# SynchConv_sch.net
KiCad netlist of a schematic drawn in Altium Designer
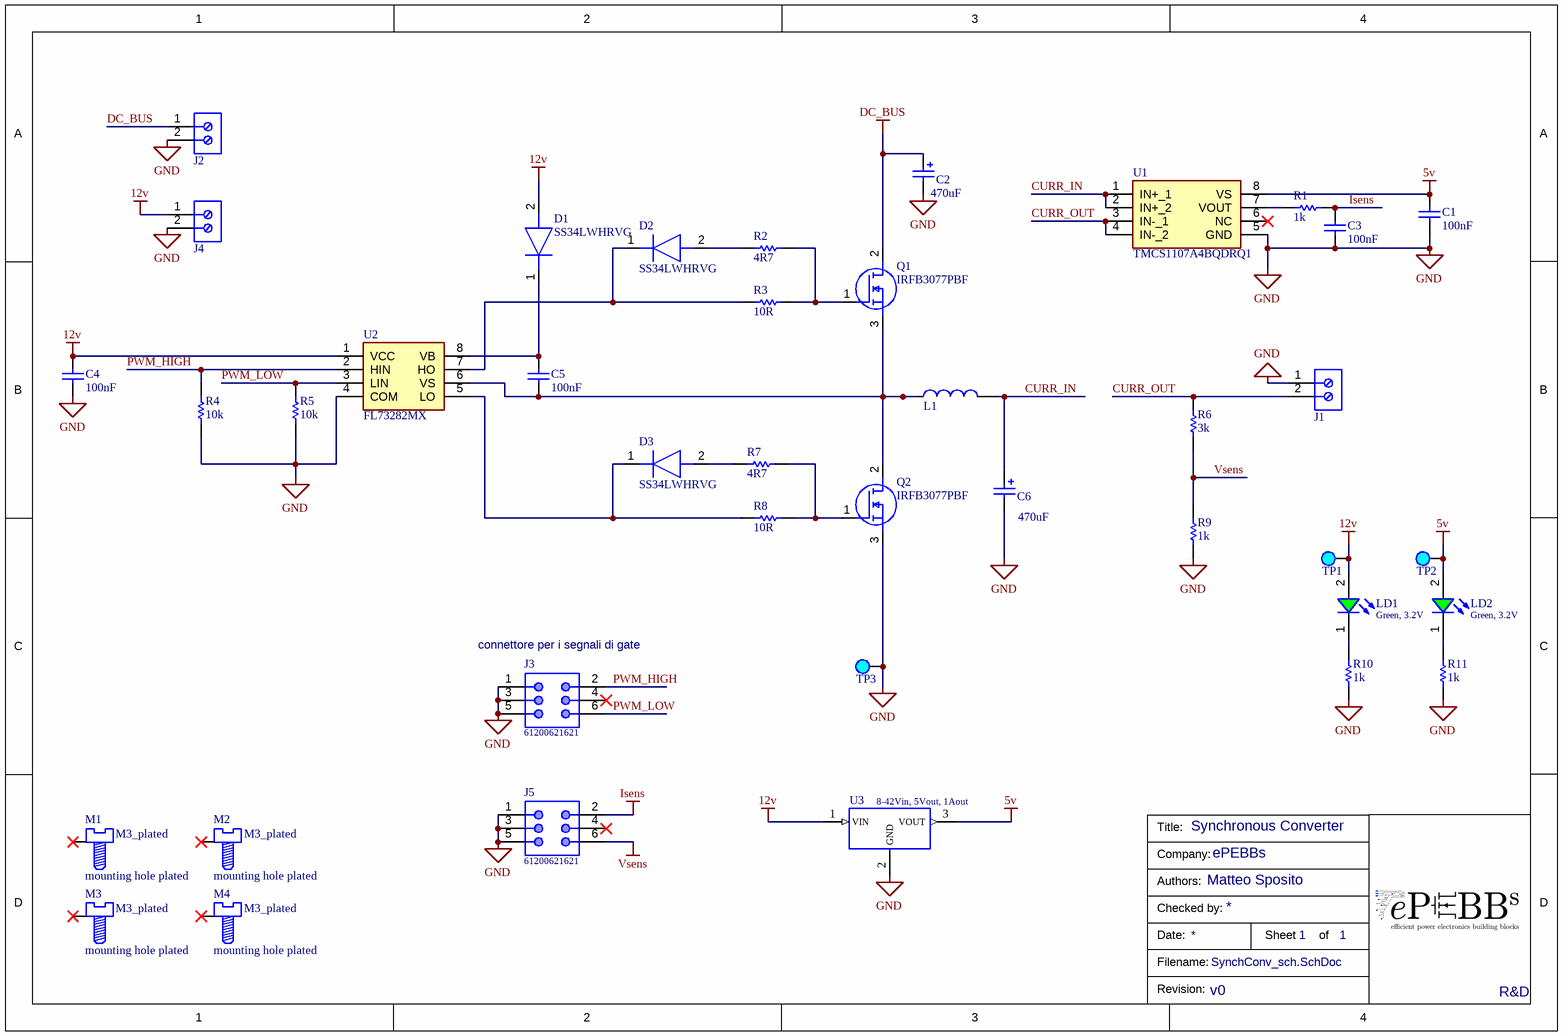
[diagram p0: SynchConv_sch.SchDoc]

(export (version "E")
  (design (tool "Eeschema 10.0.6"))
  (components
    (comp (ref "C1")
      (value "100nF")
      (footprint "CAP_0805")
      (description "capacitor 0805")
      (fields
        (field (name "MANUFACTURER PART NUMBER") "885012207098")
        (field (name "MANUFACTURER") "Wurth Elektronik")
      )
      (libsource (lib "ePEBBs_lib_sch") (part "Cap_0805"))
    )
    (comp (ref "C2")
      (value "470uF")
      (footprint "WCAP-ATG5_D13H20")
      (description "WCAP-ATG5 Aluminum Electrolytic Capacitor, Radial THT, D13xH20mm, 470uF, 63V")
      (fields
        (field (name "MANUFACTURER") "Wurth Elektronik")
        (field (name "MANUFACTURER PART NUMBER") "860020778021")
      )
      (libsource (lib "ePEBBs_lib_sch") (part "860020778021"))
    )
    (comp (ref "C3")
      (value "100nF")
      (footprint "CAP_0805")
      (description "capacitor 0805")
      (fields
        (field (name "MANUFACTURER PART NUMBER") "885012207098")
        (field (name "MANUFACTURER") "Wurth Elektronik")
      )
      (libsource (lib "ePEBBs_lib_sch") (part "Cap_0805"))
    )
    (comp (ref "C4")
      (value "100nF")
      (footprint "CAP_0805")
      (description "capacitor 0805")
      (fields
        (field (name "MANUFACTURER PART NUMBER") "885012207098")
        (field (name "MANUFACTURER") "Wurth Elektronik")
      )
      (libsource (lib "ePEBBs_lib_sch") (part "Cap_0805"))
    )
    (comp (ref "C5")
      (value "100nF")
      (footprint "CAP_0805")
      (description "capacitor 0805")
      (fields
        (field (name "MANUFACTURER PART NUMBER") "885012207098")
        (field (name "MANUFACTURER") "Wurth Elektronik")
      )
      (libsource (lib "ePEBBs_lib_sch") (part "Cap_0805"))
    )
    (comp (ref "C6")
      (value "470uF")
      (footprint "WCAP-ATG5_D13H20")
      (description "WCAP-ATG5 Aluminum Electrolytic Capacitor, Radial THT, D13xH20mm, 470uF, 63V")
      (fields
        (field (name "MANUFACTURER") "Wurth Elektronik")
        (field (name "MANUFACTURER PART NUMBER") "860020778021")
      )
      (libsource (lib "ePEBBs_lib_sch") (part "860020778021"))
    )
    (comp (ref "D1")
      (value "SS34LWHRVG")
      (footprint "SamacSys:SODFL3718X102N")
      (description "Diode")
      (fields (field (name "MOUSER PART NUMBER") "821-SS34LWHRVG"))
      (libsource (lib "*") (part "SS34LWHRVG"))
    )
    (comp (ref "D2")
      (value "SS34LWHRVG")
      (footprint "SamacSys:SODFL3718X102N")
      (description "Diode")
      (fields (field (name "MOUSER PART NUMBER") "821-SS34LWHRVG"))
      (libsource (lib "*") (part "SS34LWHRVG"))
    )
    (comp (ref "D3")
      (value "SS34LWHRVG")
      (footprint "SamacSys:SODFL3718X102N")
      (description "Diode")
      (fields (field (name "MOUSER PART NUMBER") "821-SS34LWHRVG"))
      (libsource (lib "*") (part "SS34LWHRVG"))
    )
    (comp (ref "J1")
      (value "691502710002")
      (footprint "691502710002")
      (description "WR-TBL Series 5027 Horizontal Entry Modular, Through Hole, pitch 5mm, 2p")
      (fields (field (name "MANUFACTURER") "Wurth Elektronik"))
      (libsource (lib "For IntLib") (part "691502710002"))
    )
    (comp (ref "J2")
      (value "691502710002")
      (footprint "691502710002")
      (description "WR-TBL Series 5027 Horizontal Entry Modular, Through Hole, pitch 5mm, 2p")
      (fields (field (name "MANUFACTURER") "Wurth Elektronik"))
      (libsource (lib "ePEBBs_lib_sch") (part "691502710002"))
    )
    (comp (ref "J3")
      (value "61200621621")
      (footprint "61200621621")
      (description "WR-BHD Box Header, Male PCB side, pitch 2.54mm, THT, Straight, 6p")
      (fields (field (name "MANUFACTURER") "Wurth Elektronik"))
      (libsource (lib "ePEBBs_lib_sch") (part "61200621621"))
    )
    (comp (ref "J4")
      (value "691502710002")
      (footprint "691502710002")
      (description "WR-TBL Series 5027 Horizontal Entry Modular, Through Hole, pitch 5mm, 2p")
      (fields (field (name "MANUFACTURER") "Wurth Elektronik"))
      (libsource (lib "ePEBBs_lib_sch") (part "691502710002"))
    )
    (comp (ref "J5")
      (value "61200621621")
      (footprint "61200621621")
      (description "WR-BHD Box Header, Male PCB side, pitch 2.54mm, THT, Straight, 6p")
      (fields (field (name "MANUFACTURER") "Wurth Elektronik"))
      (libsource (lib "ePEBBs_lib_sch") (part "61200621621"))
    )
    (comp (ref "L1")
      (value "59µH, 5.4A")
      (footprint "744134")
      (description "WE-SI THT Leaded Toroidal Storage Choke, 59µH, 5.4A, 0.05Ω")
      (fields
        (field (name "MANUFACTURER PART NUMBER") "744134")
        (field (name "MANUFACTURER") "Wurth Elektronik")
      )
      (libsource (lib "ePEBBs_lib_sch") (part "744134"))
    )
    (comp (ref "LD1")
      (value "Green, 3.2V")
      (footprint "WL-SMCW_0805")
      (description "WL-SMCW SMT Mono-color Chip LED Waterclear, size 0805, Green, 3.2V, 140deg")
      (fields (field (name "PART NUMBER") "150080GS75000") (field (name "PUBLISHER") "Wurth Elektronik"))
      (libsource (lib "ePEBBs_lib_sch") (part "150080GS75000"))
    )
    (comp (ref "LD2")
      (value "Green, 3.2V")
      (footprint "WL-SMCW_0805")
      (description "WL-SMCW SMT Mono-color Chip LED Waterclear, size 0805, Green, 3.2V, 140deg")
      (fields (field (name "PART NUMBER") "150080GS75000") (field (name "PUBLISHER") "Wurth Elektronik"))
      (libsource (lib "ePEBBs_lib_sch") (part "150080GS75000"))
    )
    (comp (ref "M1")
      (value "mounting hole plated")
      (footprint "M3_Mountingholes plated")
      (description "M3 plated")
      (libsource (lib "ePEBBs_lib_sch") (part "M3_MountungHole_plated"))
    )
    (comp (ref "M2")
      (value "mounting hole plated")
      (footprint "M3_Mountingholes plated")
      (description "M3 plated")
      (libsource (lib "ePEBBs_lib_sch") (part "M3_MountungHole_plated"))
    )
    (comp (ref "M3")
      (value "mounting hole plated")
      (footprint "M3_Mountingholes plated")
      (description "M3 plated")
      (libsource (lib "ePEBBs_lib_sch") (part "M3_MountungHole_plated"))
    )
    (comp (ref "M4")
      (value "mounting hole plated")
      (footprint "M3_Mountingholes plated")
      (description "M3 plated")
      (libsource (lib "ePEBBs_lib_sch") (part "M3_MountungHole_plated"))
    )
    (comp (ref "Q1")
      (value "IRFB3077PBF")
      (footprint "SamacSys:TO254P483X1016X1994-3P")
      (description "MOSFET (N-Channel)")
      (fields (field (name "MOUSER PART NUMBER") "942-IRFB3077PBF"))
      (libsource (lib "*") (part "IRFB3077PBF"))
    )
    (comp (ref "Q2")
      (value "IRFB3077PBF")
      (footprint "SamacSys:TO254P483X1016X1994-3P")
      (description "MOSFET (N-Channel)")
      (fields (field (name "MOUSER PART NUMBER") "942-IRFB3077PBF"))
      (libsource (lib "*") (part "IRFB3077PBF"))
    )
    (comp (ref "R1")
      (value "1k")
      (footprint "Res_0805")
      (description "SMT Thick Film Resistor, size 0805, 0.125W")
      (fields (field (name "TOLERANCE") "1%"))
      (libsource (lib "ePEBBs_lib_sch") (part "Res_0805"))
    )
    (comp (ref "R2")
      (value "4R7")
      (footprint "Res_0805")
      (description "SMT Thick Film Resistor, size 0805, 0.125W")
      (fields (field (name "TOLERANCE") "1%"))
      (libsource (lib "ePEBBs_lib_sch") (part "Res_0805"))
    )
    (comp (ref "R3")
      (value "10R")
      (footprint "Res_0805")
      (description "SMT Thick Film Resistor, size 0805, 0.125W")
      (fields (field (name "TOLERANCE") "1%"))
      (libsource (lib "ePEBBs_lib_sch") (part "Res_0805"))
    )
    (comp (ref "R4")
      (value "10k")
      (footprint "Res_0805")
      (description "SMT Thick Film Resistor, size 0805, 0.125W")
      (fields (field (name "TOLERANCE") "1%"))
      (libsource (lib "ePEBBs_lib_sch") (part "Res_0805"))
    )
    (comp (ref "R5")
      (value "10k")
      (footprint "Res_0805")
      (description "SMT Thick Film Resistor, size 0805, 0.125W")
      (fields (field (name "TOLERANCE") "1%"))
      (libsource (lib "ePEBBs_lib_sch") (part "Res_0805"))
    )
    (comp (ref "R6")
      (value "3k")
      (footprint "Res_0805")
      (description "SMT Thick Film Resistor, size 0805, 0.125W")
      (fields (field (name "TOLERANCE") "1%"))
      (libsource (lib "ePEBBs_lib_sch") (part "Res_0805"))
    )
    (comp (ref "R7")
      (value "4R7")
      (footprint "Res_0805")
      (description "SMT Thick Film Resistor, size 0805, 0.125W")
      (fields (field (name "TOLERANCE") "1%"))
      (libsource (lib "ePEBBs_lib_sch") (part "Res_0805"))
    )
    (comp (ref "R8")
      (value "10R")
      (footprint "Res_0805")
      (description "SMT Thick Film Resistor, size 0805, 0.125W")
      (fields (field (name "TOLERANCE") "1%"))
      (libsource (lib "ePEBBs_lib_sch") (part "Res_0805"))
    )
    (comp (ref "R9")
      (value "1k")
      (footprint "Res_0805")
      (description "SMT Thick Film Resistor, size 0805, 0.125W")
      (fields (field (name "TOLERANCE") "1%"))
      (libsource (lib "ePEBBs_lib_sch") (part "Res_0805"))
    )
    (comp (ref "R10")
      (value "1k")
      (footprint "Res_0805")
      (description "SMT Thick Film Resistor, size 0805, 0.125W")
      (fields (field (name "TOLERANCE") "1%"))
      (libsource (lib "ePEBBs_lib_sch") (part "Res_0805"))
    )
    (comp (ref "R11")
      (value "1k")
      (footprint "Res_0805")
      (description "SMT Thick Film Resistor, size 0805, 0.125W")
      (fields (field (name "TOLERANCE") "1%"))
      (libsource (lib "ePEBBs_lib_sch") (part "Res_0805"))
    )
    (comp (ref "TP1")
      (value "TP_big")
      (footprint "TP_big")
      (description "test point big")
      (libsource (lib "ePEBBs_lib_sch") (part "TP_big"))
    )
    (comp (ref "TP2")
      (value "TP_big")
      (footprint "TP_big")
      (description "test point big")
      (libsource (lib "ePEBBs_lib_sch") (part "TP_big"))
    )
    (comp (ref "TP3")
      (value "TP_big")
      (footprint "TP_big")
      (description "test point big")
      (libsource (lib "ePEBBs_lib_sch") (part "TP_big"))
    )
    (comp (ref "U1")
      (value "TMCS1107A4BQDRQ1")
      (footprint "SOIC127P600X175-8N")
      (description "SENSOR CURRENT HALL 5.6A 8SOIC")
      (libsource (lib "ePEBBs_lib_sch") (part "TMCS1107A4BQDRQ1"))
    )
    (comp (ref "U2")
      (value "FL73282MX")
      (footprint "SOIC127P600X175-8N")
      (description "Driver di porta 900V Half-Bridge Gate Driver")
      (libsource (lib "ePEBBs_lib_sch") (part "FL73282MX"))
    )
    (comp (ref "U3")
      (value "8-42Vin, 5Vout, 1Aout")
      (footprint "173010x35")
      (description "MagI3C-FDSM Fixed Step Down Regulator Module, SIP-3, 8-36Vin, 5Vout, 1Aout")
      (fields
        (field (name "MANUFACTURER PART NUMBER") "173010542")
        (field (name "PUBLISHER") "Wurth Elektronik")
      )
      (libsource (lib "ePEBBs_lib_sch") (part "173010535"))
    )
  )
  (nets
    (net (code "1") (name "/CURR_IN") (class "Default")
      (node (ref "C6") (pin "1") (pinfunction "P_1") (pintype "passive"))
      (node (ref "L1") (pin "2") (pinfunction "2_2") (pintype "passive"))
      (node (ref "U1") (pin "1") (pinfunction "IN+_1_1") (pintype "passive"))
      (node (ref "U1") (pin "2") (pinfunction "IN+_2_2") (pintype "passive"))
    )
    (net (code "2") (name "/CURR_OUT") (class "Default")
      (node (ref "J1") (pin "2") (pinfunction "2_2") (pintype "passive"))
      (node (ref "R6") (pin "1") (pinfunction "1_1") (pintype "passive"))
      (node (ref "U1") (pin "3") (pinfunction "IN-_1_3") (pintype "passive"))
      (node (ref "U1") (pin "4") (pinfunction "IN-_2_4") (pintype "passive"))
    )
    (net (code "3") (name "/PWM_HIGH") (class "Default")
      (node (ref "J3") (pin "2") (pinfunction "2_2") (pintype "passive"))
      (node (ref "R4") (pin "2") (pinfunction "2_2") (pintype "passive"))
      (node (ref "U2") (pin "2") (pinfunction "HIN_2") (pintype "passive"))
    )
    (net (code "4") (name "/PWM_LOW") (class "Default")
      (node (ref "J3") (pin "6") (pinfunction "6_6") (pintype "passive"))
      (node (ref "R5") (pin "2") (pinfunction "2_2") (pintype "passive"))
      (node (ref "U2") (pin "3") (pinfunction "LIN_3") (pintype "passive"))
    )
    (net (code "5") (name "5v") (class "Default")
      (node (ref "C1") (pin "2") (pinfunction "2_2") (pintype "passive"))
      (node (ref "LD2") (pin "2") (pinfunction "A_2") (pintype "passive"))
      (node (ref "TP2") (pin "1") (pinfunction "1_1") (pintype "passive"))
      (node (ref "U1") (pin "8") (pinfunction "VS_8") (pintype "passive"))
      (node (ref "U3") (pin "3") (pinfunction "VOUT_3") (pintype "output"))
    )
    (net (code "6") (name "12v") (class "Default")
      (node (ref "C4") (pin "2") (pinfunction "2_2") (pintype "passive"))
      (node (ref "D1") (pin "2") (pinfunction "A_2") (pintype "passive"))
      (node (ref "J4") (pin "1") (pinfunction "1_1") (pintype "passive"))
      (node (ref "LD1") (pin "2") (pinfunction "A_2") (pintype "passive"))
      (node (ref "TP1") (pin "1") (pinfunction "1_1") (pintype "passive"))
      (node (ref "U2") (pin "1") (pinfunction "VCC_1") (pintype "passive"))
      (node (ref "U3") (pin "1") (pinfunction "VIN_1") (pintype "input"))
    )
    (net (code "7") (name "DC_BUS") (class "Default")
      (node (ref "C2") (pin "1") (pinfunction "P_1") (pintype "passive"))
      (node (ref "J2") (pin "1") (pinfunction "1_1") (pintype "passive"))
      (node (ref "Q1") (pin "2") (pinfunction "D_2") (pintype "passive"))
    )
    (net (code "8") (name "GND") (class "Default")
      (node (ref "C1") (pin "1") (pinfunction "1_1") (pintype "passive"))
      (node (ref "C2") (pin "2") (pinfunction "N_2") (pintype "passive"))
      (node (ref "C3") (pin "1") (pinfunction "1_1") (pintype "passive"))
      (node (ref "C4") (pin "1") (pinfunction "1_1") (pintype "passive"))
      (node (ref "C6") (pin "2") (pinfunction "N_2") (pintype "passive"))
      (node (ref "J1") (pin "1") (pinfunction "1_1") (pintype "passive"))
      (node (ref "J2") (pin "2") (pinfunction "2_2") (pintype "passive"))
      (node (ref "J3") (pin "1") (pinfunction "1_1") (pintype "passive"))
      (node (ref "J3") (pin "3") (pinfunction "3_3") (pintype "passive"))
      (node (ref "J3") (pin "5") (pinfunction "5_5") (pintype "passive"))
      (node (ref "J4") (pin "2") (pinfunction "2_2") (pintype "passive"))
      (node (ref "J5") (pin "1") (pinfunction "1_1") (pintype "passive"))
      (node (ref "J5") (pin "3") (pinfunction "3_3") (pintype "passive"))
      (node (ref "J5") (pin "5") (pinfunction "5_5") (pintype "passive"))
      (node (ref "Q2") (pin "3") (pinfunction "S_3") (pintype "passive"))
      (node (ref "R10") (pin "1") (pinfunction "1_1") (pintype "passive"))
      (node (ref "R11") (pin "1") (pinfunction "1_1") (pintype "passive"))
      (node (ref "R4") (pin "1") (pinfunction "1_1") (pintype "passive"))
      (node (ref "R5") (pin "1") (pinfunction "1_1") (pintype "passive"))
      (node (ref "R9") (pin "2") (pinfunction "2_2") (pintype "passive"))
      (node (ref "TP3") (pin "1") (pinfunction "1_1") (pintype "passive"))
      (node (ref "U1") (pin "5") (pinfunction "GND_5") (pintype "passive"))
      (node (ref "U2") (pin "4") (pinfunction "COM_4") (pintype "passive"))
      (node (ref "U3") (pin "2") (pinfunction "GND_2") (pintype "passive"))
    )
    (net (code "9") (name "Isens") (class "Default")
      (node (ref "C3") (pin "2") (pinfunction "2_2") (pintype "passive"))
      (node (ref "J5") (pin "2") (pinfunction "2_2") (pintype "passive"))
      (node (ref "R1") (pin "1") (pinfunction "1_1") (pintype "passive"))
    )
    (net (code "10") (name "Net-(D1-K)") (class "Default")
      (node (ref "C5") (pin "2") (pinfunction "2_2") (pintype "passive"))
      (node (ref "D1") (pin "1") (pinfunction "K_1") (pintype "passive"))
      (node (ref "U2") (pin "8") (pinfunction "VB_8") (pintype "passive"))
    )
    (net (code "11") (name "Net-(D2-A)") (class "Default")
      (node (ref "D2") (pin "2") (pinfunction "A_2") (pintype "passive"))
      (node (ref "R2") (pin "1") (pinfunction "1_1") (pintype "passive"))
    )
    (net (code "12") (name "Net-(D2-K)") (class "Default")
      (node (ref "D2") (pin "1") (pinfunction "K_1") (pintype "passive"))
      (node (ref "R3") (pin "2") (pinfunction "2_2") (pintype "passive"))
      (node (ref "U2") (pin "7") (pinfunction "HO_7") (pintype "passive"))
    )
    (net (code "13") (name "Net-(D3-A)") (class "Default")
      (node (ref "D3") (pin "2") (pinfunction "A_2") (pintype "passive"))
      (node (ref "R7") (pin "1") (pinfunction "1_1") (pintype "passive"))
    )
    (net (code "14") (name "Net-(D3-K)") (class "Default")
      (node (ref "D3") (pin "1") (pinfunction "K_1") (pintype "passive"))
      (node (ref "R8") (pin "2") (pinfunction "2_2") (pintype "passive"))
      (node (ref "U2") (pin "5") (pinfunction "LO_5") (pintype "passive"))
    )
    (net (code "15") (name "Net-(LD1-K)") (class "Default")
      (node (ref "LD1") (pin "1") (pinfunction "K_1") (pintype "passive"))
      (node (ref "R10") (pin "2") (pinfunction "2_2") (pintype "passive"))
    )
    (net (code "16") (name "Net-(LD2-K)") (class "Default")
      (node (ref "LD2") (pin "1") (pinfunction "K_1") (pintype "passive"))
      (node (ref "R11") (pin "2") (pinfunction "2_2") (pintype "passive"))
    )
    (net (code "17") (name "Net-(Q1-G)") (class "Default")
      (node (ref "Q1") (pin "1") (pinfunction "G_1") (pintype "passive"))
      (node (ref "R2") (pin "2") (pinfunction "2_2") (pintype "passive"))
      (node (ref "R3") (pin "1") (pinfunction "1_1") (pintype "passive"))
    )
    (net (code "18") (name "Net-(Q1-S)") (class "Default")
      (node (ref "C5") (pin "1") (pinfunction "1_1") (pintype "passive"))
      (node (ref "L1") (pin "1") (pinfunction "1_1") (pintype "passive"))
      (node (ref "Q1") (pin "3") (pinfunction "S_3") (pintype "passive"))
      (node (ref "Q2") (pin "2") (pinfunction "D_2") (pintype "passive"))
      (node (ref "U2") (pin "6") (pinfunction "VS_6") (pintype "passive"))
    )
    (net (code "19") (name "Net-(Q2-G)") (class "Default")
      (node (ref "Q2") (pin "1") (pinfunction "G_1") (pintype "passive"))
      (node (ref "R7") (pin "2") (pinfunction "2_2") (pintype "passive"))
      (node (ref "R8") (pin "1") (pinfunction "1_1") (pintype "passive"))
    )
    (net (code "20") (name "Net-(U1-VOUT)") (class "Default")
      (node (ref "R1") (pin "2") (pinfunction "2_2") (pintype "passive"))
      (node (ref "U1") (pin "7") (pinfunction "VOUT_7") (pintype "passive"))
    )
    (net (code "21") (name "Vsens") (class "Default")
      (node (ref "J5") (pin "6") (pinfunction "6_6") (pintype "passive"))
      (node (ref "R6") (pin "2") (pinfunction "2_2") (pintype "passive"))
      (node (ref "R9") (pin "1") (pinfunction "1_1") (pintype "passive"))
    )
    (net (code "22") (name "unconnected-(J3-Pad4)") (class "Default")
      (node (ref "J3") (pin "4") (pinfunction "4_4") (pintype "passive+no_connect"))
    )
    (net (code "23") (name "unconnected-(J5-Pad4)") (class "Default")
      (node (ref "J5") (pin "4") (pinfunction "4_4") (pintype "passive+no_connect"))
    )
    (net (code "24") (name "unconnected-(M1-Pad1)") (class "Default")
      (node (ref "M1") (pin "1") (pinfunction "1_1") (pintype "passive+no_connect"))
    )
    (net (code "25") (name "unconnected-(M2-Pad1)") (class "Default")
      (node (ref "M2") (pin "1") (pinfunction "1_1") (pintype "passive+no_connect"))
    )
    (net (code "26") (name "unconnected-(M3-Pad1)") (class "Default")
      (node (ref "M3") (pin "1") (pinfunction "1_1") (pintype "passive+no_connect"))
    )
    (net (code "27") (name "unconnected-(M4-Pad1)") (class "Default")
      (node (ref "M4") (pin "1") (pinfunction "1_1") (pintype "passive+no_connect"))
    )
    (net (code "28") (name "unconnected-(U1-NC-Pad6)") (class "Default")
      (node (ref "U1") (pin "6") (pinfunction "NC_6") (pintype "passive+no_connect"))
    )
  )
)
